# AIRControl.net
KiCad netlist of a schematic drawn in Altium Designer
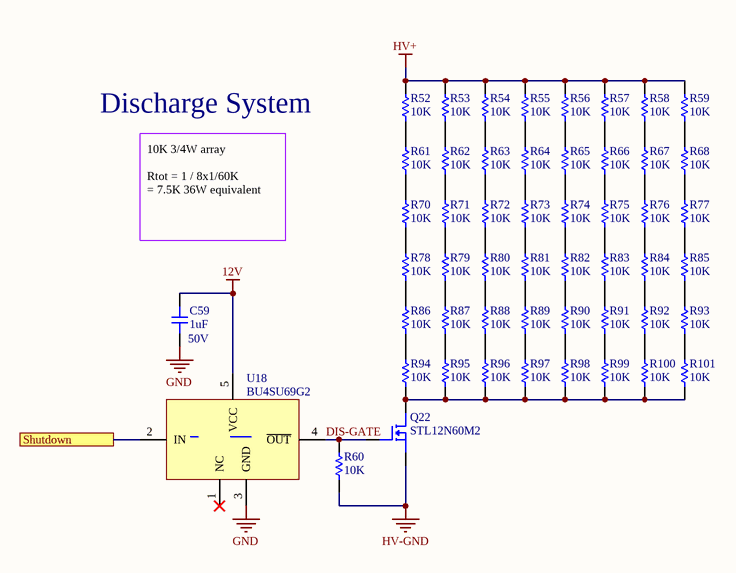
[diagram p0: AIRControl.SchDoc]

(export (version "E")
  (design (tool "Eeschema 10.0.6"))
  (components
    (comp (ref "C59")
      (value "1uF")
      (footprint "CAP-0805")
      (description "CAP CER 1UF 50V X5R 0805")
      (fields
        (field (name "MANUFACTURER") "KEMET")
        (field (name "MANUFACTURER PART NUMBER") "C0805C105K5PACTU")
        (field (name "VOLTAGE RATING") "50V")
      )
      (libsource (lib "InverterSCHLib") (part "0805-1uF-50V"))
    )
    (comp (ref "Q22")
      (value "STL12N60M2")
      (footprint "POWERFLAT-FET")
      (description "MOSFET N-CH 600V 6.5A POWERFLAT")
      (fields (field (name "MANUFACTURER") "STMicroelectronics"))
      (libsource (lib "InverterSCHLib") (part "STL12N60M2"))
    )
    (comp (ref "R52")
      (value "10K")
      (footprint "RES-1206")
      (description "RES SMD 10K OHM 1% 3/4W 1206")
      (fields
        (field (name "MANUFACTURER") "Vishay Dale")
        (field (name "MANUFACTURER PART NUMBER") "RCA120610K0FKEAHP")
      )
      (libsource (lib "InverterSCHLib") (part "1206-10KR"))
    )
    (comp (ref "R53")
      (value "10K")
      (footprint "RES-1206")
      (description "RES SMD 10K OHM 1% 3/4W 1206")
      (fields
        (field (name "MANUFACTURER") "Vishay Dale")
        (field (name "MANUFACTURER PART NUMBER") "RCA120610K0FKEAHP")
      )
      (libsource (lib "InverterSCHLib") (part "1206-10KR"))
    )
    (comp (ref "R54")
      (value "10K")
      (footprint "RES-1206")
      (description "RES SMD 10K OHM 1% 3/4W 1206")
      (fields
        (field (name "MANUFACTURER") "Vishay Dale")
        (field (name "MANUFACTURER PART NUMBER") "RCA120610K0FKEAHP")
      )
      (libsource (lib "InverterSCHLib") (part "1206-10KR"))
    )
    (comp (ref "R55")
      (value "10K")
      (footprint "RES-1206")
      (description "RES SMD 10K OHM 1% 3/4W 1206")
      (fields
        (field (name "MANUFACTURER") "Vishay Dale")
        (field (name "MANUFACTURER PART NUMBER") "RCA120610K0FKEAHP")
      )
      (libsource (lib "InverterSCHLib") (part "1206-10KR"))
    )
    (comp (ref "R56")
      (value "10K")
      (footprint "RES-1206")
      (description "RES SMD 10K OHM 1% 3/4W 1206")
      (fields
        (field (name "MANUFACTURER") "Vishay Dale")
        (field (name "MANUFACTURER PART NUMBER") "RCA120610K0FKEAHP")
      )
      (libsource (lib "InverterSCHLib") (part "1206-10KR"))
    )
    (comp (ref "R57")
      (value "10K")
      (footprint "RES-1206")
      (description "RES SMD 10K OHM 1% 3/4W 1206")
      (fields
        (field (name "MANUFACTURER") "Vishay Dale")
        (field (name "MANUFACTURER PART NUMBER") "RCA120610K0FKEAHP")
      )
      (libsource (lib "InverterSCHLib") (part "1206-10KR"))
    )
    (comp (ref "R58")
      (value "10K")
      (footprint "RES-1206")
      (description "RES SMD 10K OHM 1% 3/4W 1206")
      (fields
        (field (name "MANUFACTURER") "Vishay Dale")
        (field (name "MANUFACTURER PART NUMBER") "RCA120610K0FKEAHP")
      )
      (libsource (lib "InverterSCHLib") (part "1206-10KR"))
    )
    (comp (ref "R59")
      (value "10K")
      (footprint "RES-1206")
      (description "RES SMD 10K OHM 1% 3/4W 1206")
      (fields
        (field (name "MANUFACTURER") "Vishay Dale")
        (field (name "MANUFACTURER PART NUMBER") "RCA120610K0FKEAHP")
      )
      (libsource (lib "InverterSCHLib") (part "1206-10KR"))
    )
    (comp (ref "R60")
      (value "10K")
      (footprint "RES-0603")
      (description "RES SMD 10K OHM 5% 1/10W 0603")
      (fields
        (field (name "MANUFACTURER") "Yageo")
        (field (name "MANUFACTURER PART NUMBER") "RC0603JR-0710KL")
      )
      (libsource (lib "InverterSCHLib") (part "0603-10KR"))
    )
    (comp (ref "R61")
      (value "10K")
      (footprint "RES-1206")
      (description "RES SMD 10K OHM 1% 3/4W 1206")
      (fields
        (field (name "MANUFACTURER") "Vishay Dale")
        (field (name "MANUFACTURER PART NUMBER") "RCA120610K0FKEAHP")
      )
      (libsource (lib "InverterSCHLib") (part "1206-10KR"))
    )
    (comp (ref "R62")
      (value "10K")
      (footprint "RES-1206")
      (description "RES SMD 10K OHM 1% 3/4W 1206")
      (fields
        (field (name "MANUFACTURER") "Vishay Dale")
        (field (name "MANUFACTURER PART NUMBER") "RCA120610K0FKEAHP")
      )
      (libsource (lib "InverterSCHLib") (part "1206-10KR"))
    )
    (comp (ref "R63")
      (value "10K")
      (footprint "RES-1206")
      (description "RES SMD 10K OHM 1% 3/4W 1206")
      (fields
        (field (name "MANUFACTURER") "Vishay Dale")
        (field (name "MANUFACTURER PART NUMBER") "RCA120610K0FKEAHP")
      )
      (libsource (lib "InverterSCHLib") (part "1206-10KR"))
    )
    (comp (ref "R64")
      (value "10K")
      (footprint "RES-1206")
      (description "RES SMD 10K OHM 1% 3/4W 1206")
      (fields
        (field (name "MANUFACTURER") "Vishay Dale")
        (field (name "MANUFACTURER PART NUMBER") "RCA120610K0FKEAHP")
      )
      (libsource (lib "InverterSCHLib") (part "1206-10KR"))
    )
    (comp (ref "R65")
      (value "10K")
      (footprint "RES-1206")
      (description "RES SMD 10K OHM 1% 3/4W 1206")
      (fields
        (field (name "MANUFACTURER") "Vishay Dale")
        (field (name "MANUFACTURER PART NUMBER") "RCA120610K0FKEAHP")
      )
      (libsource (lib "InverterSCHLib") (part "1206-10KR"))
    )
    (comp (ref "R66")
      (value "10K")
      (footprint "RES-1206")
      (description "RES SMD 10K OHM 1% 3/4W 1206")
      (fields
        (field (name "MANUFACTURER") "Vishay Dale")
        (field (name "MANUFACTURER PART NUMBER") "RCA120610K0FKEAHP")
      )
      (libsource (lib "InverterSCHLib") (part "1206-10KR"))
    )
    (comp (ref "R67")
      (value "10K")
      (footprint "RES-1206")
      (description "RES SMD 10K OHM 1% 3/4W 1206")
      (fields
        (field (name "MANUFACTURER") "Vishay Dale")
        (field (name "MANUFACTURER PART NUMBER") "RCA120610K0FKEAHP")
      )
      (libsource (lib "InverterSCHLib") (part "1206-10KR"))
    )
    (comp (ref "R68")
      (value "10K")
      (footprint "RES-1206")
      (description "RES SMD 10K OHM 1% 3/4W 1206")
      (fields
        (field (name "MANUFACTURER") "Vishay Dale")
        (field (name "MANUFACTURER PART NUMBER") "RCA120610K0FKEAHP")
      )
      (libsource (lib "InverterSCHLib") (part "1206-10KR"))
    )
    (comp (ref "R70")
      (value "10K")
      (footprint "RES-1206")
      (description "RES SMD 10K OHM 1% 3/4W 1206")
      (fields
        (field (name "MANUFACTURER") "Vishay Dale")
        (field (name "MANUFACTURER PART NUMBER") "RCA120610K0FKEAHP")
      )
      (libsource (lib "InverterSCHLib") (part "1206-10KR"))
    )
    (comp (ref "R71")
      (value "10K")
      (footprint "RES-1206")
      (description "RES SMD 10K OHM 1% 3/4W 1206")
      (fields
        (field (name "MANUFACTURER") "Vishay Dale")
        (field (name "MANUFACTURER PART NUMBER") "RCA120610K0FKEAHP")
      )
      (libsource (lib "InverterSCHLib") (part "1206-10KR"))
    )
    (comp (ref "R72")
      (value "10K")
      (footprint "RES-1206")
      (description "RES SMD 10K OHM 1% 3/4W 1206")
      (fields
        (field (name "MANUFACTURER") "Vishay Dale")
        (field (name "MANUFACTURER PART NUMBER") "RCA120610K0FKEAHP")
      )
      (libsource (lib "InverterSCHLib") (part "1206-10KR"))
    )
    (comp (ref "R73")
      (value "10K")
      (footprint "RES-1206")
      (description "RES SMD 10K OHM 1% 3/4W 1206")
      (fields
        (field (name "MANUFACTURER") "Vishay Dale")
        (field (name "MANUFACTURER PART NUMBER") "RCA120610K0FKEAHP")
      )
      (libsource (lib "InverterSCHLib") (part "1206-10KR"))
    )
    (comp (ref "R74")
      (value "10K")
      (footprint "RES-1206")
      (description "RES SMD 10K OHM 1% 3/4W 1206")
      (fields
        (field (name "MANUFACTURER") "Vishay Dale")
        (field (name "MANUFACTURER PART NUMBER") "RCA120610K0FKEAHP")
      )
      (libsource (lib "InverterSCHLib") (part "1206-10KR"))
    )
    (comp (ref "R75")
      (value "10K")
      (footprint "RES-1206")
      (description "RES SMD 10K OHM 1% 3/4W 1206")
      (fields
        (field (name "MANUFACTURER") "Vishay Dale")
        (field (name "MANUFACTURER PART NUMBER") "RCA120610K0FKEAHP")
      )
      (libsource (lib "InverterSCHLib") (part "1206-10KR"))
    )
    (comp (ref "R76")
      (value "10K")
      (footprint "RES-1206")
      (description "RES SMD 10K OHM 1% 3/4W 1206")
      (fields
        (field (name "MANUFACTURER") "Vishay Dale")
        (field (name "MANUFACTURER PART NUMBER") "RCA120610K0FKEAHP")
      )
      (libsource (lib "InverterSCHLib") (part "1206-10KR"))
    )
    (comp (ref "R77")
      (value "10K")
      (footprint "RES-1206")
      (description "RES SMD 10K OHM 1% 3/4W 1206")
      (fields
        (field (name "MANUFACTURER") "Vishay Dale")
        (field (name "MANUFACTURER PART NUMBER") "RCA120610K0FKEAHP")
      )
      (libsource (lib "InverterSCHLib") (part "1206-10KR"))
    )
    (comp (ref "R78")
      (value "10K")
      (footprint "RES-1206")
      (description "RES SMD 10K OHM 1% 3/4W 1206")
      (fields
        (field (name "MANUFACTURER") "Vishay Dale")
        (field (name "MANUFACTURER PART NUMBER") "RCA120610K0FKEAHP")
      )
      (libsource (lib "InverterSCHLib") (part "1206-10KR"))
    )
    (comp (ref "R79")
      (value "10K")
      (footprint "RES-1206")
      (description "RES SMD 10K OHM 1% 3/4W 1206")
      (fields
        (field (name "MANUFACTURER") "Vishay Dale")
        (field (name "MANUFACTURER PART NUMBER") "RCA120610K0FKEAHP")
      )
      (libsource (lib "InverterSCHLib") (part "1206-10KR"))
    )
    (comp (ref "R80")
      (value "10K")
      (footprint "RES-1206")
      (description "RES SMD 10K OHM 1% 3/4W 1206")
      (fields
        (field (name "MANUFACTURER") "Vishay Dale")
        (field (name "MANUFACTURER PART NUMBER") "RCA120610K0FKEAHP")
      )
      (libsource (lib "InverterSCHLib") (part "1206-10KR"))
    )
    (comp (ref "R81")
      (value "10K")
      (footprint "RES-1206")
      (description "RES SMD 10K OHM 1% 3/4W 1206")
      (fields
        (field (name "MANUFACTURER") "Vishay Dale")
        (field (name "MANUFACTURER PART NUMBER") "RCA120610K0FKEAHP")
      )
      (libsource (lib "InverterSCHLib") (part "1206-10KR"))
    )
    (comp (ref "R82")
      (value "10K")
      (footprint "RES-1206")
      (description "RES SMD 10K OHM 1% 3/4W 1206")
      (fields
        (field (name "MANUFACTURER") "Vishay Dale")
        (field (name "MANUFACTURER PART NUMBER") "RCA120610K0FKEAHP")
      )
      (libsource (lib "InverterSCHLib") (part "1206-10KR"))
    )
    (comp (ref "R83")
      (value "10K")
      (footprint "RES-1206")
      (description "RES SMD 10K OHM 1% 3/4W 1206")
      (fields
        (field (name "MANUFACTURER") "Vishay Dale")
        (field (name "MANUFACTURER PART NUMBER") "RCA120610K0FKEAHP")
      )
      (libsource (lib "InverterSCHLib") (part "1206-10KR"))
    )
    (comp (ref "R84")
      (value "10K")
      (footprint "RES-1206")
      (description "RES SMD 10K OHM 1% 3/4W 1206")
      (fields
        (field (name "MANUFACTURER") "Vishay Dale")
        (field (name "MANUFACTURER PART NUMBER") "RCA120610K0FKEAHP")
      )
      (libsource (lib "InverterSCHLib") (part "1206-10KR"))
    )
    (comp (ref "R85")
      (value "10K")
      (footprint "RES-1206")
      (description "RES SMD 10K OHM 1% 3/4W 1206")
      (fields
        (field (name "MANUFACTURER") "Vishay Dale")
        (field (name "MANUFACTURER PART NUMBER") "RCA120610K0FKEAHP")
      )
      (libsource (lib "InverterSCHLib") (part "1206-10KR"))
    )
    (comp (ref "R86")
      (value "10K")
      (footprint "RES-1206")
      (description "RES SMD 10K OHM 1% 3/4W 1206")
      (fields
        (field (name "MANUFACTURER") "Vishay Dale")
        (field (name "MANUFACTURER PART NUMBER") "RCA120610K0FKEAHP")
      )
      (libsource (lib "InverterSCHLib") (part "1206-10KR"))
    )
    (comp (ref "R87")
      (value "10K")
      (footprint "RES-1206")
      (description "RES SMD 10K OHM 1% 3/4W 1206")
      (fields
        (field (name "MANUFACTURER") "Vishay Dale")
        (field (name "MANUFACTURER PART NUMBER") "RCA120610K0FKEAHP")
      )
      (libsource (lib "InverterSCHLib") (part "1206-10KR"))
    )
    (comp (ref "R88")
      (value "10K")
      (footprint "RES-1206")
      (description "RES SMD 10K OHM 1% 3/4W 1206")
      (fields
        (field (name "MANUFACTURER") "Vishay Dale")
        (field (name "MANUFACTURER PART NUMBER") "RCA120610K0FKEAHP")
      )
      (libsource (lib "InverterSCHLib") (part "1206-10KR"))
    )
    (comp (ref "R89")
      (value "10K")
      (footprint "RES-1206")
      (description "RES SMD 10K OHM 1% 3/4W 1206")
      (fields
        (field (name "MANUFACTURER") "Vishay Dale")
        (field (name "MANUFACTURER PART NUMBER") "RCA120610K0FKEAHP")
      )
      (libsource (lib "InverterSCHLib") (part "1206-10KR"))
    )
    (comp (ref "R90")
      (value "10K")
      (footprint "RES-1206")
      (description "RES SMD 10K OHM 1% 3/4W 1206")
      (fields
        (field (name "MANUFACTURER") "Vishay Dale")
        (field (name "MANUFACTURER PART NUMBER") "RCA120610K0FKEAHP")
      )
      (libsource (lib "InverterSCHLib") (part "1206-10KR"))
    )
    (comp (ref "R91")
      (value "10K")
      (footprint "RES-1206")
      (description "RES SMD 10K OHM 1% 3/4W 1206")
      (fields
        (field (name "MANUFACTURER") "Vishay Dale")
        (field (name "MANUFACTURER PART NUMBER") "RCA120610K0FKEAHP")
      )
      (libsource (lib "InverterSCHLib") (part "1206-10KR"))
    )
    (comp (ref "R92")
      (value "10K")
      (footprint "RES-1206")
      (description "RES SMD 10K OHM 1% 3/4W 1206")
      (fields
        (field (name "MANUFACTURER") "Vishay Dale")
        (field (name "MANUFACTURER PART NUMBER") "RCA120610K0FKEAHP")
      )
      (libsource (lib "InverterSCHLib") (part "1206-10KR"))
    )
    (comp (ref "R93")
      (value "10K")
      (footprint "RES-1206")
      (description "RES SMD 10K OHM 1% 3/4W 1206")
      (fields
        (field (name "MANUFACTURER") "Vishay Dale")
        (field (name "MANUFACTURER PART NUMBER") "RCA120610K0FKEAHP")
      )
      (libsource (lib "InverterSCHLib") (part "1206-10KR"))
    )
    (comp (ref "R94")
      (value "10K")
      (footprint "RES-1206")
      (description "RES SMD 10K OHM 1% 3/4W 1206")
      (fields
        (field (name "MANUFACTURER") "Vishay Dale")
        (field (name "MANUFACTURER PART NUMBER") "RCA120610K0FKEAHP")
      )
      (libsource (lib "InverterSCHLib") (part "1206-10KR"))
    )
    (comp (ref "R95")
      (value "10K")
      (footprint "RES-1206")
      (description "RES SMD 10K OHM 1% 3/4W 1206")
      (fields
        (field (name "MANUFACTURER") "Vishay Dale")
        (field (name "MANUFACTURER PART NUMBER") "RCA120610K0FKEAHP")
      )
      (libsource (lib "InverterSCHLib") (part "1206-10KR"))
    )
    (comp (ref "R96")
      (value "10K")
      (footprint "RES-1206")
      (description "RES SMD 10K OHM 1% 3/4W 1206")
      (fields
        (field (name "MANUFACTURER") "Vishay Dale")
        (field (name "MANUFACTURER PART NUMBER") "RCA120610K0FKEAHP")
      )
      (libsource (lib "InverterSCHLib") (part "1206-10KR"))
    )
    (comp (ref "R97")
      (value "10K")
      (footprint "RES-1206")
      (description "RES SMD 10K OHM 1% 3/4W 1206")
      (fields
        (field (name "MANUFACTURER") "Vishay Dale")
        (field (name "MANUFACTURER PART NUMBER") "RCA120610K0FKEAHP")
      )
      (libsource (lib "InverterSCHLib") (part "1206-10KR"))
    )
    (comp (ref "R98")
      (value "10K")
      (footprint "RES-1206")
      (description "RES SMD 10K OHM 1% 3/4W 1206")
      (fields
        (field (name "MANUFACTURER") "Vishay Dale")
        (field (name "MANUFACTURER PART NUMBER") "RCA120610K0FKEAHP")
      )
      (libsource (lib "InverterSCHLib") (part "1206-10KR"))
    )
    (comp (ref "R99")
      (value "10K")
      (footprint "RES-1206")
      (description "RES SMD 10K OHM 1% 3/4W 1206")
      (fields
        (field (name "MANUFACTURER") "Vishay Dale")
        (field (name "MANUFACTURER PART NUMBER") "RCA120610K0FKEAHP")
      )
      (libsource (lib "InverterSCHLib") (part "1206-10KR"))
    )
    (comp (ref "R100")
      (value "10K")
      (footprint "RES-1206")
      (description "RES SMD 10K OHM 1% 3/4W 1206")
      (fields
        (field (name "MANUFACTURER") "Vishay Dale")
        (field (name "MANUFACTURER PART NUMBER") "RCA120610K0FKEAHP")
      )
      (libsource (lib "InverterSCHLib") (part "1206-10KR"))
    )
    (comp (ref "R101")
      (value "10K")
      (footprint "RES-1206")
      (description "RES SMD 10K OHM 1% 3/4W 1206")
      (fields
        (field (name "MANUFACTURER") "Vishay Dale")
        (field (name "MANUFACTURER PART NUMBER") "RCA120610K0FKEAHP")
      )
      (libsource (lib "InverterSCHLib") (part "1206-10KR"))
    )
    (comp (ref "U18")
      (value "BU4SU69G2")
      (footprint "SSOP5")
      (description "IC INVERTER 1CH 1-INP 5SSOP")
      (fields (field (name "MANUFACTURER") "Rohm") (field (name "MANUFACTURER PART NUMBER") "BU4SU69G2-TR"))
      (libsource (lib "InverterSCHLib") (part "BU4SU69G2"))
    )
  )
  (nets
    (net (code "1") (name "/DIS-GATE") (class "Default")
      (node (ref "Q22") (pin "1") (pinfunction "1_1") (pintype "passive"))
      (node (ref "R60") (pin "2") (pinfunction "2_2") (pintype "passive"))
      (node (ref "U18") (pin "4") (pinfunction "~{OUT}_4") (pintype "passive"))
    )
    (net (code "2") (name "/Shutdown") (class "Default")
      (node (ref "U18") (pin "2") (pinfunction "IN_2") (pintype "passive"))
    )
    (net (code "3") (name "12V") (class "Default")
      (node (ref "C59") (pin "2") (pinfunction "2_2") (pintype "passive"))
      (node (ref "U18") (pin "5") (pinfunction "VCC_5") (pintype "passive"))
    )
    (net (code "4") (name "GND") (class "Default")
      (node (ref "C59") (pin "1") (pinfunction "1_1") (pintype "passive"))
      (node (ref "U18") (pin "3") (pinfunction "GND_3") (pintype "passive"))
    )
    (net (code "5") (name "HV+") (class "Default")
      (node (ref "R52") (pin "2") (pinfunction "2_2") (pintype "passive"))
      (node (ref "R53") (pin "2") (pinfunction "2_2") (pintype "passive"))
      (node (ref "R54") (pin "2") (pinfunction "2_2") (pintype "passive"))
      (node (ref "R55") (pin "2") (pinfunction "2_2") (pintype "passive"))
      (node (ref "R56") (pin "2") (pinfunction "2_2") (pintype "passive"))
      (node (ref "R57") (pin "2") (pinfunction "2_2") (pintype "passive"))
      (node (ref "R58") (pin "2") (pinfunction "2_2") (pintype "passive"))
      (node (ref "R59") (pin "2") (pinfunction "2_2") (pintype "passive"))
    )
    (net (code "6") (name "HV-GND") (class "Default")
      (node (ref "Q22") (pin "3") (pinfunction "3_3") (pintype "passive"))
      (node (ref "R60") (pin "1") (pinfunction "1_1") (pintype "passive"))
    )
    (net (code "7") (name "Net-(Q22-Pad2)") (class "Default")
      (node (ref "Q22") (pin "2") (pinfunction "2_2") (pintype "passive"))
      (node (ref "R100") (pin "1") (pinfunction "1_1") (pintype "passive"))
      (node (ref "R101") (pin "1") (pinfunction "1_1") (pintype "passive"))
      (node (ref "R94") (pin "1") (pinfunction "1_1") (pintype "passive"))
      (node (ref "R95") (pin "1") (pinfunction "1_1") (pintype "passive"))
      (node (ref "R96") (pin "1") (pinfunction "1_1") (pintype "passive"))
      (node (ref "R97") (pin "1") (pinfunction "1_1") (pintype "passive"))
      (node (ref "R98") (pin "1") (pinfunction "1_1") (pintype "passive"))
      (node (ref "R99") (pin "1") (pinfunction "1_1") (pintype "passive"))
    )
    (net (code "8") (name "Net-(R52-Pad1)") (class "Default")
      (node (ref "R52") (pin "1") (pinfunction "1_1") (pintype "passive"))
      (node (ref "R61") (pin "2") (pinfunction "2_2") (pintype "passive"))
    )
    (net (code "9") (name "Net-(R53-Pad1)") (class "Default")
      (node (ref "R53") (pin "1") (pinfunction "1_1") (pintype "passive"))
      (node (ref "R62") (pin "2") (pinfunction "2_2") (pintype "passive"))
    )
    (net (code "10") (name "Net-(R54-Pad1)") (class "Default")
      (node (ref "R54") (pin "1") (pinfunction "1_1") (pintype "passive"))
      (node (ref "R63") (pin "2") (pinfunction "2_2") (pintype "passive"))
    )
    (net (code "11") (name "Net-(R55-Pad1)") (class "Default")
      (node (ref "R55") (pin "1") (pinfunction "1_1") (pintype "passive"))
      (node (ref "R64") (pin "2") (pinfunction "2_2") (pintype "passive"))
    )
    (net (code "12") (name "Net-(R56-Pad1)") (class "Default")
      (node (ref "R56") (pin "1") (pinfunction "1_1") (pintype "passive"))
      (node (ref "R65") (pin "2") (pinfunction "2_2") (pintype "passive"))
    )
    (net (code "13") (name "Net-(R57-Pad1)") (class "Default")
      (node (ref "R57") (pin "1") (pinfunction "1_1") (pintype "passive"))
      (node (ref "R66") (pin "2") (pinfunction "2_2") (pintype "passive"))
    )
    (net (code "14") (name "Net-(R58-Pad1)") (class "Default")
      (node (ref "R58") (pin "1") (pinfunction "1_1") (pintype "passive"))
      (node (ref "R67") (pin "2") (pinfunction "2_2") (pintype "passive"))
    )
    (net (code "15") (name "Net-(R59-Pad1)") (class "Default")
      (node (ref "R59") (pin "1") (pinfunction "1_1") (pintype "passive"))
      (node (ref "R68") (pin "2") (pinfunction "2_2") (pintype "passive"))
    )
    (net (code "16") (name "Net-(R61-Pad1)") (class "Default")
      (node (ref "R61") (pin "1") (pinfunction "1_1") (pintype "passive"))
      (node (ref "R70") (pin "2") (pinfunction "2_2") (pintype "passive"))
    )
    (net (code "17") (name "Net-(R62-Pad1)") (class "Default")
      (node (ref "R62") (pin "1") (pinfunction "1_1") (pintype "passive"))
      (node (ref "R71") (pin "2") (pinfunction "2_2") (pintype "passive"))
    )
    (net (code "18") (name "Net-(R63-Pad1)") (class "Default")
      (node (ref "R63") (pin "1") (pinfunction "1_1") (pintype "passive"))
      (node (ref "R72") (pin "2") (pinfunction "2_2") (pintype "passive"))
    )
    (net (code "19") (name "Net-(R64-Pad1)") (class "Default")
      (node (ref "R64") (pin "1") (pinfunction "1_1") (pintype "passive"))
      (node (ref "R73") (pin "2") (pinfunction "2_2") (pintype "passive"))
    )
    (net (code "20") (name "Net-(R65-Pad1)") (class "Default")
      (node (ref "R65") (pin "1") (pinfunction "1_1") (pintype "passive"))
      (node (ref "R74") (pin "2") (pinfunction "2_2") (pintype "passive"))
    )
    (net (code "21") (name "Net-(R66-Pad1)") (class "Default")
      (node (ref "R66") (pin "1") (pinfunction "1_1") (pintype "passive"))
      (node (ref "R75") (pin "2") (pinfunction "2_2") (pintype "passive"))
    )
    (net (code "22") (name "Net-(R67-Pad1)") (class "Default")
      (node (ref "R67") (pin "1") (pinfunction "1_1") (pintype "passive"))
      (node (ref "R76") (pin "2") (pinfunction "2_2") (pintype "passive"))
    )
    (net (code "23") (name "Net-(R68-Pad1)") (class "Default")
      (node (ref "R68") (pin "1") (pinfunction "1_1") (pintype "passive"))
      (node (ref "R77") (pin "2") (pinfunction "2_2") (pintype "passive"))
    )
    (net (code "24") (name "Net-(R70-Pad1)") (class "Default")
      (node (ref "R70") (pin "1") (pinfunction "1_1") (pintype "passive"))
      (node (ref "R78") (pin "2") (pinfunction "2_2") (pintype "passive"))
    )
    (net (code "25") (name "Net-(R71-Pad1)") (class "Default")
      (node (ref "R71") (pin "1") (pinfunction "1_1") (pintype "passive"))
      (node (ref "R79") (pin "2") (pinfunction "2_2") (pintype "passive"))
    )
    (net (code "26") (name "Net-(R72-Pad1)") (class "Default")
      (node (ref "R72") (pin "1") (pinfunction "1_1") (pintype "passive"))
      (node (ref "R80") (pin "2") (pinfunction "2_2") (pintype "passive"))
    )
    (net (code "27") (name "Net-(R73-Pad1)") (class "Default")
      (node (ref "R73") (pin "1") (pinfunction "1_1") (pintype "passive"))
      (node (ref "R81") (pin "2") (pinfunction "2_2") (pintype "passive"))
    )
    (net (code "28") (name "Net-(R74-Pad1)") (class "Default")
      (node (ref "R74") (pin "1") (pinfunction "1_1") (pintype "passive"))
      (node (ref "R82") (pin "2") (pinfunction "2_2") (pintype "passive"))
    )
    (net (code "29") (name "Net-(R75-Pad1)") (class "Default")
      (node (ref "R75") (pin "1") (pinfunction "1_1") (pintype "passive"))
      (node (ref "R83") (pin "2") (pinfunction "2_2") (pintype "passive"))
    )
    (net (code "30") (name "Net-(R76-Pad1)") (class "Default")
      (node (ref "R76") (pin "1") (pinfunction "1_1") (pintype "passive"))
      (node (ref "R84") (pin "2") (pinfunction "2_2") (pintype "passive"))
    )
    (net (code "31") (name "Net-(R77-Pad1)") (class "Default")
      (node (ref "R77") (pin "1") (pinfunction "1_1") (pintype "passive"))
      (node (ref "R85") (pin "2") (pinfunction "2_2") (pintype "passive"))
    )
    (net (code "32") (name "Net-(R78-Pad1)") (class "Default")
      (node (ref "R78") (pin "1") (pinfunction "1_1") (pintype "passive"))
      (node (ref "R86") (pin "2") (pinfunction "2_2") (pintype "passive"))
    )
    (net (code "33") (name "Net-(R79-Pad1)") (class "Default")
      (node (ref "R79") (pin "1") (pinfunction "1_1") (pintype "passive"))
      (node (ref "R87") (pin "2") (pinfunction "2_2") (pintype "passive"))
    )
    (net (code "34") (name "Net-(R80-Pad1)") (class "Default")
      (node (ref "R80") (pin "1") (pinfunction "1_1") (pintype "passive"))
      (node (ref "R88") (pin "2") (pinfunction "2_2") (pintype "passive"))
    )
    (net (code "35") (name "Net-(R81-Pad1)") (class "Default")
      (node (ref "R81") (pin "1") (pinfunction "1_1") (pintype "passive"))
      (node (ref "R89") (pin "2") (pinfunction "2_2") (pintype "passive"))
    )
    (net (code "36") (name "Net-(R82-Pad1)") (class "Default")
      (node (ref "R82") (pin "1") (pinfunction "1_1") (pintype "passive"))
      (node (ref "R90") (pin "2") (pinfunction "2_2") (pintype "passive"))
    )
    (net (code "37") (name "Net-(R83-Pad1)") (class "Default")
      (node (ref "R83") (pin "1") (pinfunction "1_1") (pintype "passive"))
      (node (ref "R91") (pin "2") (pinfunction "2_2") (pintype "passive"))
    )
    (net (code "38") (name "Net-(R84-Pad1)") (class "Default")
      (node (ref "R84") (pin "1") (pinfunction "1_1") (pintype "passive"))
      (node (ref "R92") (pin "2") (pinfunction "2_2") (pintype "passive"))
    )
    (net (code "39") (name "Net-(R85-Pad1)") (class "Default")
      (node (ref "R85") (pin "1") (pinfunction "1_1") (pintype "passive"))
      (node (ref "R93") (pin "2") (pinfunction "2_2") (pintype "passive"))
    )
    (net (code "40") (name "Net-(R86-Pad1)") (class "Default")
      (node (ref "R86") (pin "1") (pinfunction "1_1") (pintype "passive"))
      (node (ref "R94") (pin "2") (pinfunction "2_2") (pintype "passive"))
    )
    (net (code "41") (name "Net-(R87-Pad1)") (class "Default")
      (node (ref "R87") (pin "1") (pinfunction "1_1") (pintype "passive"))
      (node (ref "R95") (pin "2") (pinfunction "2_2") (pintype "passive"))
    )
    (net (code "42") (name "Net-(R88-Pad1)") (class "Default")
      (node (ref "R88") (pin "1") (pinfunction "1_1") (pintype "passive"))
      (node (ref "R96") (pin "2") (pinfunction "2_2") (pintype "passive"))
    )
    (net (code "43") (name "Net-(R89-Pad1)") (class "Default")
      (node (ref "R89") (pin "1") (pinfunction "1_1") (pintype "passive"))
      (node (ref "R97") (pin "2") (pinfunction "2_2") (pintype "passive"))
    )
    (net (code "44") (name "Net-(R90-Pad1)") (class "Default")
      (node (ref "R90") (pin "1") (pinfunction "1_1") (pintype "passive"))
      (node (ref "R98") (pin "2") (pinfunction "2_2") (pintype "passive"))
    )
    (net (code "45") (name "Net-(R91-Pad1)") (class "Default")
      (node (ref "R91") (pin "1") (pinfunction "1_1") (pintype "passive"))
      (node (ref "R99") (pin "2") (pinfunction "2_2") (pintype "passive"))
    )
    (net (code "46") (name "Net-(R100-Pad2)") (class "Default")
      (node (ref "R100") (pin "2") (pinfunction "2_2") (pintype "passive"))
      (node (ref "R92") (pin "1") (pinfunction "1_1") (pintype "passive"))
    )
    (net (code "47") (name "Net-(R101-Pad2)") (class "Default")
      (node (ref "R101") (pin "2") (pinfunction "2_2") (pintype "passive"))
      (node (ref "R93") (pin "1") (pinfunction "1_1") (pintype "passive"))
    )
    (net (code "48") (name "unconnected-(U18-NC-Pad1)") (class "Default")
      (node (ref "U18") (pin "1") (pinfunction "NC_1") (pintype "passive+no_connect"))
    )
  )
)
